# KC_BaseBoard4CompareTest.net
KiCad netlist of a schematic drawn in Altium Designer
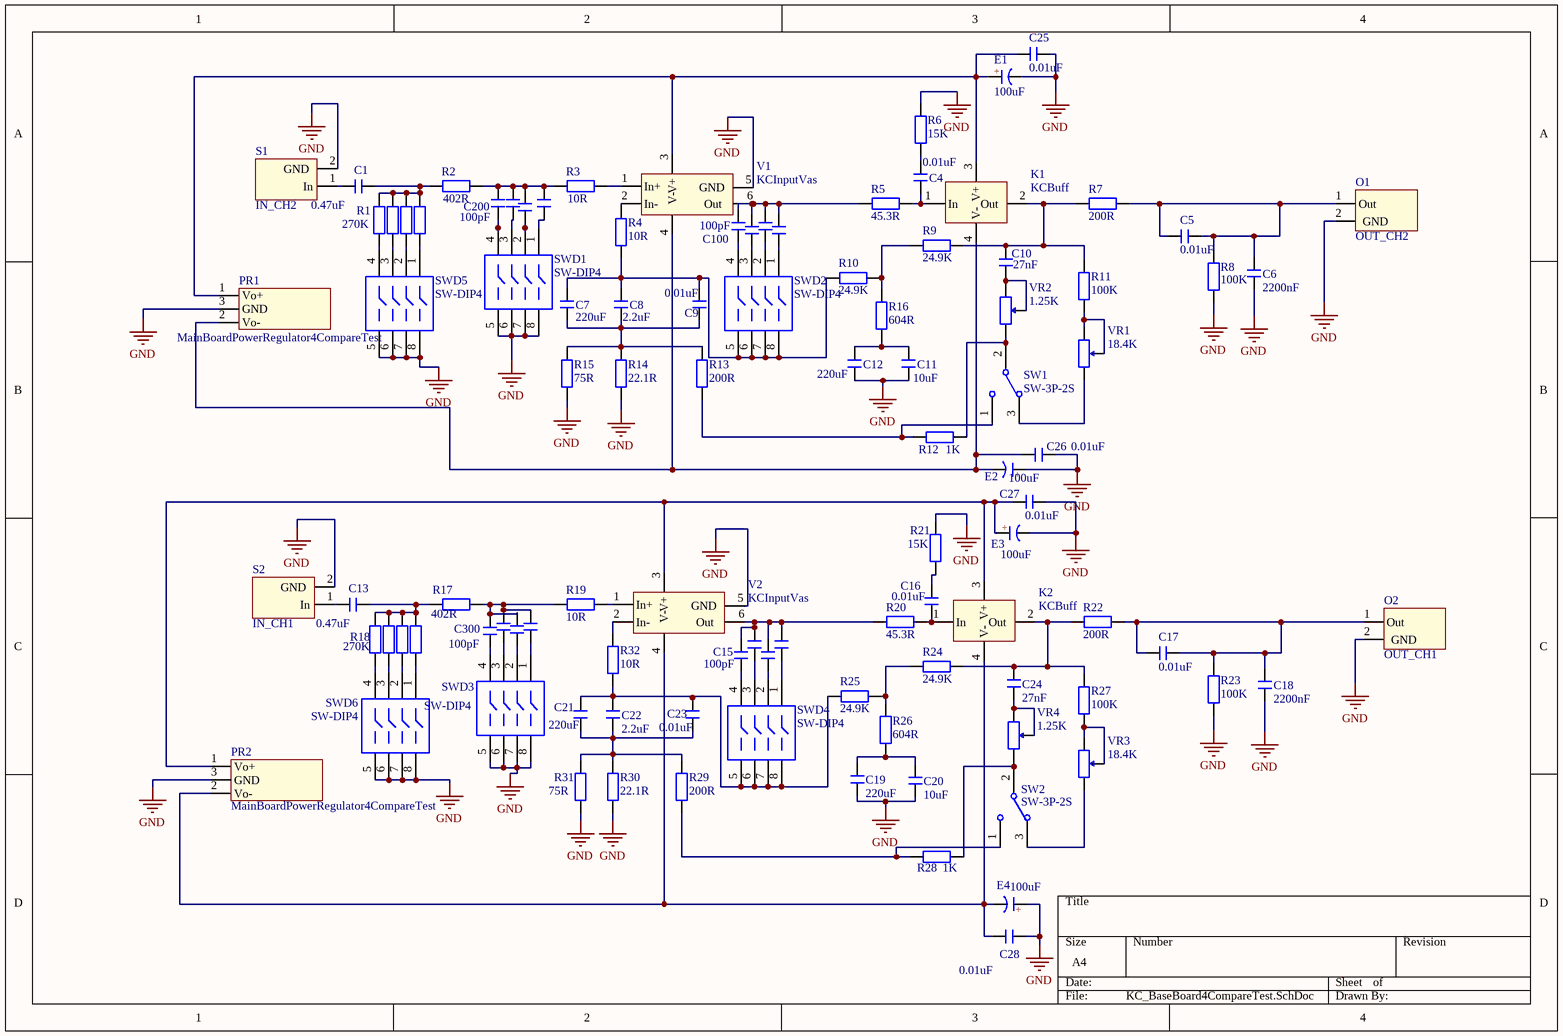
[diagram p0: KC_BaseBoard4CompareTest.SchDoc]

(export (version "E")
  (design (tool "Eeschema 10.0.6"))
  (components
    (comp (ref "C1")
      (value "0.47uF")
      (footprint "CBB 50*30*30")
      (description "CBB电容")
      (fields (field (name "版权归属") "源创客"))
      (libsource (lib "电阻-电容-电感") (part "C-CBB"))
    )
    (comp (ref "C4")
      (value "0.01uF")
      (footprint "CBB 6.3*6.3*5")
      (description "CBB电容")
      (fields (field (name "版权归属") "源创客"))
      (libsource (lib "电阻-电容-电感") (part "C-CBB"))
    )
    (comp (ref "C5")
      (value "0.01uF")
      (footprint "CBB 6.3*6.3*5")
      (description "CBB电容")
      (fields (field (name "版权归属") "源创客"))
      (libsource (lib "电阻-电容-电感") (part "C-CBB"))
    )
    (comp (ref "C6")
      (value "2200nF")
      (footprint "CBB 6.3*6.3*5")
      (description "CBB电容")
      (fields (field (name "版权归属") "源创客"))
      (libsource (lib "电阻-电容-电感") (part "C-CBB"))
    )
    (comp (ref "C7")
      (value "220uF")
      (footprint "CBB 6.3*6.3*5")
      (description "CBB电容")
      (fields (field (name "版权归属") "源创客"))
      (libsource (lib "电阻-电容-电感") (part "C-CBB"))
    )
    (comp (ref "C8")
      (value "2.2uF")
      (footprint "CBB 6.3*6.3*5")
      (description "CBB电容")
      (fields (field (name "版权归属") "源创客"))
      (libsource (lib "电阻-电容-电感") (part "C-CBB"))
    )
    (comp (ref "C9")
      (value "0.01uF")
      (footprint "CBB 6.3*6.3*5")
      (description "CBB电容")
      (fields (field (name "版权归属") "源创客"))
      (libsource (lib "电阻-电容-电感") (part "C-CBB"))
    )
    (comp (ref "C10")
      (value "27nF")
      (footprint "CBB 6.3*6.3*5")
      (description "CBB电容")
      (fields (field (name "版权归属") "源创客"))
      (libsource (lib "电阻-电容-电感") (part "C-CBB"))
    )
    (comp (ref "C11")
      (value "10uF")
      (footprint "CBB 6.3*6.3*5")
      (description "CBB电容")
      (fields (field (name "版权归属") "源创客"))
      (libsource (lib "电阻-电容-电感") (part "C-CBB"))
    )
    (comp (ref "C12")
      (value "220uF")
      (footprint "CBB 6.3*6.3*5")
      (description "CBB电容")
      (fields (field (name "版权归属") "源创客"))
      (libsource (lib "电阻-电容-电感") (part "C-CBB"))
    )
    (comp (ref "C13")
      (value "0.47uF")
      (footprint "CBB 50*30*30")
      (description "CBB电容")
      (fields (field (name "版权归属") "源创客"))
      (libsource (lib "电阻-电容-电感") (part "C-CBB"))
    )
    (comp (ref "C15")
      (value "100pF")
      (footprint "CBB 6.3*6.3*5")
      (description "CBB电容")
      (fields (field (name "版权归属") "源创客"))
      (libsource (lib "电阻-电容-电感") (part "C-CBB"))
    )
    (comp (ref "C16")
      (value "0.01uF")
      (footprint "CBB 6.3*6.3*5")
      (description "CBB电容")
      (fields (field (name "版权归属") "源创客"))
      (libsource (lib "电阻-电容-电感") (part "C-CBB"))
    )
    (comp (ref "C17")
      (value "0.01uF")
      (footprint "CBB 6.3*6.3*5")
      (description "CBB电容")
      (fields (field (name "版权归属") "源创客"))
      (libsource (lib "电阻-电容-电感") (part "C-CBB"))
    )
    (comp (ref "C18")
      (value "2200nF")
      (footprint "CBB 6.3*6.3*5")
      (description "CBB电容")
      (fields (field (name "版权归属") "源创客"))
      (libsource (lib "电阻-电容-电感") (part "C-CBB"))
    )
    (comp (ref "C19")
      (value "220uF")
      (footprint "CBB 6.3*6.3*5")
      (description "CBB电容")
      (fields (field (name "版权归属") "源创客"))
      (libsource (lib "电阻-电容-电感") (part "C-CBB"))
    )
    (comp (ref "C20")
      (value "10uF")
      (footprint "CBB 6.3*6.3*5")
      (description "CBB电容")
      (fields (field (name "版权归属") "源创客"))
      (libsource (lib "电阻-电容-电感") (part "C-CBB"))
    )
    (comp (ref "C21")
      (value "220uF")
      (footprint "CBB 6.3*6.3*5")
      (description "CBB电容")
      (fields (field (name "版权归属") "源创客"))
      (libsource (lib "电阻-电容-电感") (part "C-CBB"))
    )
    (comp (ref "C22")
      (value "2.2uF")
      (footprint "CBB 6.3*6.3*5")
      (description "CBB电容")
      (fields (field (name "版权归属") "源创客"))
      (libsource (lib "电阻-电容-电感") (part "C-CBB"))
    )
    (comp (ref "C23")
      (value "0.01uF")
      (footprint "CBB 6.3*6.3*5")
      (description "CBB电容")
      (fields (field (name "版权归属") "源创客"))
      (libsource (lib "电阻-电容-电感") (part "C-CBB"))
    )
    (comp (ref "C24")
      (value "27nF")
      (footprint "CBB 6.3*6.3*5")
      (description "CBB电容")
      (fields (field (name "版权归属") "源创客"))
      (libsource (lib "电阻-电容-电感") (part "C-CBB"))
    )
    (comp (ref "C25")
      (value "0.01uF")
      (footprint "CBB 6.3*6.3*5")
      (description "CBB电容")
      (fields (field (name "版权归属") "源创客"))
      (libsource (lib "电阻-电容-电感") (part "C-CBB"))
    )
    (comp (ref "C26")
      (value "0.01uF")
      (footprint "CBB 6.3*6.3*5")
      (description "CBB电容")
      (fields (field (name "版权归属") "源创客"))
      (libsource (lib "电阻-电容-电感") (part "C-CBB"))
    )
    (comp (ref "C27")
      (value "0.01uF")
      (footprint "CBB 6.3*6.3*5")
      (description "CBB电容")
      (fields (field (name "版权归属") "源创客"))
      (libsource (lib "电阻-电容-电感") (part "C-CBB"))
    )
    (comp (ref "C28")
      (value "0.01uF")
      (footprint "CBB 6.3*6.3*5")
      (description "CBB电容")
      (fields (field (name "版权归属") "源创客"))
      (libsource (lib "电阻-电容-电感") (part "C-CBB"))
    )
    (comp (ref "C100")
      (value "100pF")
      (footprint "CBB 6.3*6.3*5")
      (description "CBB电容")
      (fields (field (name "版权归属") "源创客"))
      (libsource (lib "电阻-电容-电感") (part "C-CBB"))
    )
    (comp (ref "C101")
      (value "100pF")
      (footprint "CBB 6.3*6.3*5")
      (description "CBB电容")
      (fields (field (name "版权归属") "源创客"))
      (libsource (lib "电阻-电容-电感") (part "C-CBB"))
    )
    (comp (ref "C102")
      (value "100pF")
      (footprint "CBB 6.3*6.3*5")
      (description "CBB电容")
      (fields (field (name "版权归属") "源创客"))
      (libsource (lib "电阻-电容-电感") (part "C-CBB"))
    )
    (comp (ref "C103")
      (value "20pF")
      (footprint "CBB 6.3*6.3*5")
      (description "CBB电容")
      (fields (field (name "版权归属") "源创客"))
      (libsource (lib "电阻-电容-电感") (part "C-CBB"))
    )
    (comp (ref "C200")
      (value "100pF")
      (footprint "CBB 6.3*6.3*5")
      (description "CBB电容")
      (fields (field (name "版权归属") "源创客"))
      (libsource (lib "电阻-电容-电感") (part "C-CBB"))
    )
    (comp (ref "C201")
      (value "100pF")
      (footprint "CBB 6.3*6.3*5")
      (description "CBB电容")
      (fields (field (name "版权归属") "源创客"))
      (libsource (lib "电阻-电容-电感") (part "C-CBB"))
    )
    (comp (ref "C202")
      (value "100pF")
      (footprint "CBB 6.3*6.3*5")
      (description "CBB电容")
      (fields (field (name "版权归属") "源创客"))
      (libsource (lib "电阻-电容-电感") (part "C-CBB"))
    )
    (comp (ref "C203")
      (value "20pF")
      (footprint "CBB 6.3*6.3*5")
      (description "CBB电容")
      (fields (field (name "版权归属") "源创客"))
      (libsource (lib "电阻-电容-电感") (part "C-CBB"))
    )
    (comp (ref "C300")
      (value "100pF")
      (footprint "CBB 6.3*6.3*5")
      (description "CBB电容")
      (fields (field (name "版权归属") "源创客"))
      (libsource (lib "电阻-电容-电感") (part "C-CBB"))
    )
    (comp (ref "C301")
      (value "100pF")
      (footprint "CBB 6.3*6.3*5")
      (description "CBB电容")
      (fields (field (name "版权归属") "源创客"))
      (libsource (lib "电阻-电容-电感") (part "C-CBB"))
    )
    (comp (ref "C302")
      (value "100pF")
      (footprint "CBB 6.3*6.3*5")
      (description "CBB电容")
      (fields (field (name "版权归属") "源创客"))
      (libsource (lib "电阻-电容-电感") (part "C-CBB"))
    )
    (comp (ref "C303")
      (value "20pF")
      (footprint "CBB 6.3*6.3*5")
      (description "CBB电容")
      (fields (field (name "版权归属") "源创客"))
      (libsource (lib "电阻-电容-电感") (part "C-CBB"))
    )
    (comp (ref "C401")
      (value "100pF")
      (footprint "CBB 6.3*6.3*5")
      (description "CBB电容")
      (fields (field (name "版权归属") "源创客"))
      (libsource (lib "电阻-电容-电感") (part "C-CBB"))
    )
    (comp (ref "C402")
      (value "100pF")
      (footprint "CBB 6.3*6.3*5")
      (description "CBB电容")
      (fields (field (name "版权归属") "源创客"))
      (libsource (lib "电阻-电容-电感") (part "C-CBB"))
    )
    (comp (ref "C403")
      (value "20pF")
      (footprint "CBB 6.3*6.3*5")
      (description "CBB电容")
      (fields (field (name "版权归属") "源创客"))
      (libsource (lib "电阻-电容-电感") (part "C-CBB"))
    )
    (comp (ref "E1")
      (value "100uF")
      (footprint "CAP 5.0*10*20")
      (description "直插电解电容")
      (fields (field (name "版权归属") "源创客"))
      (libsource (lib "电阻-电容-电感") (part "C-CAP"))
    )
    (comp (ref "E2")
      (value "100uF")
      (footprint "CAP 5.0*10*20")
      (description "直插电解电容")
      (fields (field (name "版权归属") "源创客"))
      (libsource (lib "电阻-电容-电感") (part "C-CAP"))
    )
    (comp (ref "E3")
      (value "100uF")
      (footprint "CAP 5.0*10*20")
      (description "直插电解电容")
      (fields (field (name "版权归属") "源创客"))
      (libsource (lib "电阻-电容-电感") (part "C-CAP"))
    )
    (comp (ref "E4")
      (value "100uF")
      (footprint "CAP 5.0*10*20")
      (description "直插电解电容")
      (fields (field (name "版权归属") "源创客"))
      (libsource (lib "电阻-电容-电感") (part "C-CAP"))
    )
    (comp (ref "K1")
      (value "KCBuff")
      (footprint "KCBuff_M4")
      (description "King Cello Buffer Stage")
      (libsource (lib "KC_amp") (part "KCBuff"))
    )
    (comp (ref "K2")
      (value "KCBuff")
      (footprint "KCBuff_M4")
      (description "King Cello Buffer Stage")
      (libsource (lib "KC_amp") (part "KCBuff"))
    )
    (comp (ref "O1")
      (value "OUT_CH2")
      (footprint "Signal_Terminal")
      (description "Signal Out")
      (libsource (lib "KC_amp") (part "Signal_Out"))
    )
    (comp (ref "O2")
      (value "OUT_CH1")
      (footprint "Signal_Terminal")
      (description "Signal Out")
      (libsource (lib "KC_amp") (part "Signal_Out"))
    )
    (comp (ref "PR1")
      (value "MainBoardPowerRegulator4CompareTest")
      (footprint "KC_MBPowerReg4Compare")
      (description "King Cello Compare Test Power")
      (libsource (lib "KC_amp") (part "MainBoardPowerRegulator4CompareTest"))
    )
    (comp (ref "PR2")
      (value "MainBoardPowerRegulator4CompareTest")
      (footprint "KC_MBPowerReg4Compare")
      (description "King Cello Compare Test Power")
      (libsource (lib "KC_amp") (part "MainBoardPowerRegulator4CompareTest"))
    )
    (comp (ref "R1")
      (value "270K")
      (footprint "RS 1/2W")
      (description "直插色环电阻")
      (fields (field (name "版权归属") "源创客"))
      (libsource (lib "电阻-电容-电感") (part "R-CRR"))
    )
    (comp (ref "R2")
      (value "402R")
      (footprint "RS 1/2W")
      (description "直插色环电阻")
      (fields (field (name "版权归属") "源创客"))
      (libsource (lib "电阻-电容-电感") (part "R-CRR"))
    )
    (comp (ref "R3")
      (value "10R")
      (footprint "RS 1/2W")
      (description "直插色环电阻")
      (fields (field (name "版权归属") "源创客"))
      (libsource (lib "电阻-电容-电感") (part "R-CRR"))
    )
    (comp (ref "R4")
      (value "10R")
      (footprint "RS 1/2W")
      (description "直插色环电阻")
      (fields (field (name "版权归属") "源创客"))
      (libsource (lib "电阻-电容-电感") (part "R-CRR"))
    )
    (comp (ref "R5")
      (value "45.3R")
      (footprint "RS 1/2W")
      (description "直插色环电阻")
      (fields (field (name "版权归属") "源创客"))
      (libsource (lib "电阻-电容-电感") (part "R-CRR"))
    )
    (comp (ref "R6")
      (value "15K")
      (footprint "RS 1/2W")
      (description "直插色环电阻")
      (fields (field (name "版权归属") "源创客"))
      (libsource (lib "电阻-电容-电感") (part "R-CRR"))
    )
    (comp (ref "R7")
      (value "200R")
      (footprint "RS 1W")
      (description "直插色环电阻")
      (fields (field (name "版权归属") "源创客"))
      (libsource (lib "电阻-电容-电感") (part "R-CRR"))
    )
    (comp (ref "R8")
      (value "100K")
      (footprint "RS 1/2W")
      (description "直插色环电阻")
      (fields (field (name "版权归属") "源创客"))
      (libsource (lib "电阻-电容-电感") (part "R-CRR"))
    )
    (comp (ref "R9")
      (value "24.9K")
      (footprint "RS 1/2W")
      (description "直插色环电阻")
      (fields (field (name "版权归属") "源创客"))
      (libsource (lib "电阻-电容-电感") (part "R-CRR"))
    )
    (comp (ref "R10")
      (value "24.9K")
      (footprint "RS 1/2W")
      (description "直插色环电阻")
      (fields (field (name "版权归属") "源创客"))
      (libsource (lib "电阻-电容-电感") (part "R-CRR"))
    )
    (comp (ref "R11")
      (value "100K")
      (footprint "RS 1/2W")
      (description "直插色环电阻")
      (fields (field (name "版权归属") "源创客"))
      (libsource (lib "电阻-电容-电感") (part "R-CRR"))
    )
    (comp (ref "R12")
      (value "1K")
      (footprint "RS 1/2W")
      (description "直插色环电阻")
      (fields (field (name "版权归属") "源创客"))
      (libsource (lib "电阻-电容-电感") (part "R-CRR"))
    )
    (comp (ref "R13")
      (value "200R")
      (footprint "RS 1/2W")
      (description "直插色环电阻")
      (fields (field (name "版权归属") "源创客"))
      (libsource (lib "电阻-电容-电感") (part "R-CRR"))
    )
    (comp (ref "R14")
      (value "22.1R")
      (footprint "RS 1/2W")
      (description "直插色环电阻")
      (fields (field (name "版权归属") "源创客"))
      (libsource (lib "电阻-电容-电感") (part "R-CRR"))
    )
    (comp (ref "R15")
      (value "75R")
      (footprint "RS 1/2W")
      (description "直插色环电阻")
      (fields (field (name "版权归属") "源创客"))
      (libsource (lib "电阻-电容-电感") (part "R-CRR"))
    )
    (comp (ref "R16")
      (value "604R")
      (footprint "RS 1W")
      (description "直插色环电阻")
      (fields (field (name "版权归属") "源创客"))
      (libsource (lib "电阻-电容-电感") (part "R-CRR"))
    )
    (comp (ref "R17")
      (value "402R")
      (footprint "RS 1/2W")
      (description "直插色环电阻")
      (fields (field (name "版权归属") "源创客"))
      (libsource (lib "电阻-电容-电感") (part "R-CRR"))
    )
    (comp (ref "R18")
      (value "270K")
      (footprint "RS 1/2W")
      (description "直插色环电阻")
      (fields (field (name "版权归属") "源创客"))
      (libsource (lib "电阻-电容-电感") (part "R-CRR"))
    )
    (comp (ref "R19")
      (value "10R")
      (footprint "RS 1/2W")
      (description "直插色环电阻")
      (fields (field (name "版权归属") "源创客"))
      (libsource (lib "电阻-电容-电感") (part "R-CRR"))
    )
    (comp (ref "R20")
      (value "45.3R")
      (footprint "RS 1/2W")
      (description "直插色环电阻")
      (fields (field (name "版权归属") "源创客"))
      (libsource (lib "电阻-电容-电感") (part "R-CRR"))
    )
    (comp (ref "R21")
      (value "15K")
      (footprint "RS 1/2W")
      (description "直插色环电阻")
      (fields (field (name "版权归属") "源创客"))
      (libsource (lib "电阻-电容-电感") (part "R-CRR"))
    )
    (comp (ref "R22")
      (value "200R")
      (footprint "RS 1W")
      (description "直插色环电阻")
      (fields (field (name "版权归属") "源创客"))
      (libsource (lib "电阻-电容-电感") (part "R-CRR"))
    )
    (comp (ref "R23")
      (value "100K")
      (footprint "RS 1/2W")
      (description "直插色环电阻")
      (fields (field (name "版权归属") "源创客"))
      (libsource (lib "电阻-电容-电感") (part "R-CRR"))
    )
    (comp (ref "R24")
      (value "24.9K")
      (footprint "RS 1/2W")
      (description "直插色环电阻")
      (fields (field (name "版权归属") "源创客"))
      (libsource (lib "电阻-电容-电感") (part "R-CRR"))
    )
    (comp (ref "R25")
      (value "24.9K")
      (footprint "RS 1/2W")
      (description "直插色环电阻")
      (fields (field (name "版权归属") "源创客"))
      (libsource (lib "电阻-电容-电感") (part "R-CRR"))
    )
    (comp (ref "R26")
      (value "604R")
      (footprint "RS 1W")
      (description "直插色环电阻")
      (fields (field (name "版权归属") "源创客"))
      (libsource (lib "电阻-电容-电感") (part "R-CRR"))
    )
    (comp (ref "R27")
      (value "100K")
      (footprint "RS 1/2W")
      (description "直插色环电阻")
      (fields (field (name "版权归属") "源创客"))
      (libsource (lib "电阻-电容-电感") (part "R-CRR"))
    )
    (comp (ref "R28")
      (value "1K")
      (footprint "RS 1/2W")
      (description "直插色环电阻")
      (fields (field (name "版权归属") "源创客"))
      (libsource (lib "电阻-电容-电感") (part "R-CRR"))
    )
    (comp (ref "R29")
      (value "200R")
      (footprint "RS 1/2W")
      (description "直插色环电阻")
      (fields (field (name "版权归属") "源创客"))
      (libsource (lib "电阻-电容-电感") (part "R-CRR"))
    )
    (comp (ref "R30")
      (value "22.1R")
      (footprint "RS 1/2W")
      (description "直插色环电阻")
      (fields (field (name "版权归属") "源创客"))
      (libsource (lib "电阻-电容-电感") (part "R-CRR"))
    )
    (comp (ref "R31")
      (value "75R")
      (footprint "RS 1/2W")
      (description "直插色环电阻")
      (fields (field (name "版权归属") "源创客"))
      (libsource (lib "电阻-电容-电感") (part "R-CRR"))
    )
    (comp (ref "R32")
      (value "10R")
      (footprint "RS 1/2W")
      (description "直插色环电阻")
      (fields (field (name "版权归属") "源创客"))
      (libsource (lib "电阻-电容-电感") (part "R-CRR"))
    )
    (comp (ref "R101")
      (value "182K")
      (footprint "RS 1/2W")
      (description "直插色环电阻")
      (fields (field (name "版权归属") "源创客"))
      (libsource (lib "电阻-电容-电感") (part "R-CRR"))
    )
    (comp (ref "R102")
      (value "100K")
      (footprint "RS 1/2W")
      (description "直插色环电阻")
      (fields (field (name "版权归属") "源创客"))
      (libsource (lib "电阻-电容-电感") (part "R-CRR"))
    )
    (comp (ref "R103")
      (value "47K")
      (footprint "RS 1/2W")
      (description "直插色环电阻")
      (fields (field (name "版权归属") "源创客"))
      (libsource (lib "电阻-电容-电感") (part "R-CRR"))
    )
    (comp (ref "R181")
      (value "182K")
      (footprint "RS 1/2W")
      (description "直插色环电阻")
      (fields (field (name "版权归属") "源创客"))
      (libsource (lib "电阻-电容-电感") (part "R-CRR"))
    )
    (comp (ref "R182")
      (value "100K")
      (footprint "RS 1/2W")
      (description "直插色环电阻")
      (fields (field (name "版权归属") "源创客"))
      (libsource (lib "电阻-电容-电感") (part "R-CRR"))
    )
    (comp (ref "R183")
      (value "47K")
      (footprint "RS 1/2W")
      (description "直插色环电阻")
      (fields (field (name "版权归属") "源创客"))
      (libsource (lib "电阻-电容-电感") (part "R-CRR"))
    )
    (comp (ref "S1")
      (value "IN_CH2")
      (footprint "Signal_Terminal")
      (description "Signal In")
      (libsource (lib "KC_amp") (part "Signal_In"))
    )
    (comp (ref "S2")
      (value "IN_CH1")
      (footprint "Signal_Terminal")
      (description "Signal In")
      (libsource (lib "KC_amp") (part "Signal_In"))
    )
    (comp (ref "SW1")
      (value "SW-3P-2S")
      (footprint "SS-12D06")
      (description "3 Pin 2 Switch")
      (libsource (lib "Connectors") (part "SW-3P-2S"))
    )
    (comp (ref "SW2")
      (value "SW-3P-2S")
      (footprint "SS-12D06")
      (description "3 Pin 2 Switch")
      (libsource (lib "Connectors") (part "SW-3P-2S"))
    )
    (comp (ref "SWD1")
      (value "SW-DIP4")
      (footprint "DIP-8")
      (description "DIP Switch")
      (fields (field (name "PUBLISHER") "Altium Limited"))
      (libsource (lib "Miscellaneous Devices") (part "SW-DIP4"))
    )
    (comp (ref "SWD2")
      (value "SW-DIP4")
      (footprint "DIP-8")
      (description "DIP Switch")
      (fields (field (name "PUBLISHER") "Altium Limited"))
      (libsource (lib "Miscellaneous Devices") (part "SW-DIP4"))
    )
    (comp (ref "SWD3")
      (value "SW-DIP4")
      (footprint "DIP-8")
      (description "DIP Switch")
      (fields (field (name "PUBLISHER") "Altium Limited"))
      (libsource (lib "Miscellaneous Devices") (part "SW-DIP4"))
    )
    (comp (ref "SWD4")
      (value "SW-DIP4")
      (footprint "DIP-8")
      (description "DIP Switch")
      (fields (field (name "PUBLISHER") "Altium Limited"))
      (libsource (lib "Miscellaneous Devices") (part "SW-DIP4"))
    )
    (comp (ref "SWD5")
      (value "SW-DIP4")
      (footprint "DIP-8")
      (description "DIP Switch")
      (fields (field (name "PUBLISHER") "Altium Limited"))
      (libsource (lib "Miscellaneous Devices") (part "SW-DIP4"))
    )
    (comp (ref "SWD6")
      (value "SW-DIP4")
      (footprint "DIP-8")
      (description "DIP Switch")
      (fields (field (name "PUBLISHER") "Altium Limited"))
      (libsource (lib "Miscellaneous Devices") (part "SW-DIP4"))
    )
    (comp (ref "V1")
      (value "KCInputVas")
      (footprint "KCIn_VAS_M4")
      (description "King Cello Input Stage and VAS")
      (libsource (lib "KC_amp") (part "KCInputVas"))
    )
    (comp (ref "V2")
      (value "KCInputVas")
      (footprint "KCIn_VAS_M4")
      (description "King Cello Input Stage and VAS")
      (libsource (lib "KC_amp") (part "KCInputVas"))
    )
    (comp (ref "VR1")
      (value "18.4K")
      (footprint "RS 1/2W-VR")
      (description "直插可调电阻-顶调")
      (libsource (lib "电阻-电容-电感") (part "VR-W"))
    )
    (comp (ref "VR2")
      (value "1.25K")
      (footprint "RS 1/2W-VR")
      (description "直插可调电阻-顶调")
      (libsource (lib "电阻-电容-电感") (part "VR-W"))
    )
    (comp (ref "VR3")
      (value "18.4K")
      (footprint "RS 1/2W-VR")
      (description "直插可调电阻-顶调")
      (libsource (lib "电阻-电容-电感") (part "VR-W"))
    )
    (comp (ref "VR4")
      (value "1.25K")
      (footprint "RS 1/2W-VR")
      (description "直插可调电阻-顶调")
      (libsource (lib "电阻-电容-电感") (part "VR-W"))
    )
  )
  (nets
    (net (code "1") (name "GND") (class "Default")
      (node (ref "C11") (pin "1") (pinfunction "1_1") (pintype "passive"))
      (node (ref "C12") (pin "1") (pinfunction "1_1") (pintype "passive"))
      (node (ref "C18") (pin "2") (pinfunction "2_2") (pintype "passive"))
      (node (ref "C19") (pin "2") (pinfunction "2_2") (pintype "passive"))
      (node (ref "C20") (pin "2") (pinfunction "2_2") (pintype "passive"))
      (node (ref "C25") (pin "2") (pinfunction "2_2") (pintype "passive"))
      (node (ref "C26") (pin "2") (pinfunction "2_2") (pintype "passive"))
      (node (ref "C27") (pin "2") (pinfunction "2_2") (pintype "passive"))
      (node (ref "C28") (pin "2") (pinfunction "2_2") (pintype "passive"))
      (node (ref "C6") (pin "1") (pinfunction "1_1") (pintype "passive"))
      (node (ref "E1") (pin "2") (pinfunction "K_2") (pintype "passive"))
      (node (ref "E2") (pin "1") (pinfunction "A_1") (pintype "passive"))
      (node (ref "E3") (pin "2") (pinfunction "K_2") (pintype "passive"))
      (node (ref "E4") (pin "1") (pinfunction "A_1") (pintype "passive"))
      (node (ref "O1") (pin "2") (pinfunction "GND_2") (pintype "passive"))
      (node (ref "O2") (pin "2") (pinfunction "GND_2") (pintype "passive"))
      (node (ref "PR1") (pin "3") (pinfunction "GND_3") (pintype "passive"))
      (node (ref "PR2") (pin "3") (pinfunction "GND_3") (pintype "passive"))
      (node (ref "R14") (pin "1") (pinfunction "1_1") (pintype "passive"))
      (node (ref "R15") (pin "1") (pinfunction "1_1") (pintype "passive"))
      (node (ref "R21") (pin "2") (pinfunction "2_2") (pintype "passive"))
      (node (ref "R23") (pin "2") (pinfunction "2_2") (pintype "passive"))
      (node (ref "R30") (pin "1") (pinfunction "1_1") (pintype "passive"))
      (node (ref "R31") (pin "1") (pinfunction "1_1") (pintype "passive"))
      (node (ref "R6") (pin "1") (pinfunction "1_1") (pintype "passive"))
      (node (ref "R8") (pin "1") (pinfunction "1_1") (pintype "passive"))
      (node (ref "S1") (pin "2") (pinfunction "GND_2") (pintype "passive"))
      (node (ref "S2") (pin "2") (pinfunction "GND_2") (pintype "passive"))
      (node (ref "SWD1") (pin "5") (pinfunction "5_5") (pintype "passive"))
      (node (ref "SWD1") (pin "6") (pinfunction "6_6") (pintype "passive"))
      (node (ref "SWD1") (pin "7") (pinfunction "7_7") (pintype "passive"))
      (node (ref "SWD1") (pin "8") (pinfunction "8_8") (pintype "passive"))
      (node (ref "SWD3") (pin "5") (pinfunction "5_5") (pintype "passive"))
      (node (ref "SWD3") (pin "6") (pinfunction "6_6") (pintype "passive"))
      (node (ref "SWD3") (pin "7") (pinfunction "7_7") (pintype "passive"))
      (node (ref "SWD3") (pin "8") (pinfunction "8_8") (pintype "passive"))
      (node (ref "SWD5") (pin "5") (pinfunction "5_5") (pintype "passive"))
      (node (ref "SWD5") (pin "6") (pinfunction "6_6") (pintype "passive"))
      (node (ref "SWD5") (pin "7") (pinfunction "7_7") (pintype "passive"))
      (node (ref "SWD5") (pin "8") (pinfunction "8_8") (pintype "passive"))
      (node (ref "SWD6") (pin "5") (pinfunction "5_5") (pintype "passive"))
      (node (ref "SWD6") (pin "6") (pinfunction "6_6") (pintype "passive"))
      (node (ref "SWD6") (pin "7") (pinfunction "7_7") (pintype "passive"))
      (node (ref "SWD6") (pin "8") (pinfunction "8_8") (pintype "passive"))
      (node (ref "V1") (pin "5") (pinfunction "GND_5") (pintype "passive"))
      (node (ref "V2") (pin "5") (pinfunction "GND_5") (pintype "passive"))
    )
    (net (code "2") (name "Net-(C1-Pad2)") (class "Default")
      (node (ref "C1") (pin "2") (pinfunction "2_2") (pintype "passive"))
      (node (ref "R1") (pin "2") (pinfunction "2_2") (pintype "passive"))
      (node (ref "R101") (pin "2") (pinfunction "2_2") (pintype "passive"))
      (node (ref "R102") (pin "2") (pinfunction "2_2") (pintype "passive"))
      (node (ref "R103") (pin "2") (pinfunction "2_2") (pintype "passive"))
      (node (ref "R2") (pin "1") (pinfunction "1_1") (pintype "passive"))
    )
    (net (code "3") (name "Net-(C4-Pad2)") (class "Default")
      (node (ref "C4") (pin "2") (pinfunction "2_2") (pintype "passive"))
      (node (ref "R6") (pin "2") (pinfunction "2_2") (pintype "passive"))
    )
    (net (code "4") (name "Net-(C7-Pad1)") (class "Default")
      (node (ref "C7") (pin "1") (pinfunction "1_1") (pintype "passive"))
      (node (ref "C8") (pin "1") (pinfunction "1_1") (pintype "passive"))
      (node (ref "C9") (pin "1") (pinfunction "1_1") (pintype "passive"))
      (node (ref "R13") (pin "2") (pinfunction "2_2") (pintype "passive"))
      (node (ref "R14") (pin "2") (pinfunction "2_2") (pintype "passive"))
      (node (ref "R15") (pin "2") (pinfunction "2_2") (pintype "passive"))
    )
    (net (code "5") (name "Net-(C7-Pad2)") (class "Default")
      (node (ref "C7") (pin "2") (pinfunction "2_2") (pintype "passive"))
      (node (ref "C8") (pin "2") (pinfunction "2_2") (pintype "passive"))
      (node (ref "C9") (pin "2") (pinfunction "2_2") (pintype "passive"))
      (node (ref "R10") (pin "2") (pinfunction "2_2") (pintype "passive"))
      (node (ref "R4") (pin "1") (pinfunction "1_1") (pintype "passive"))
      (node (ref "SWD2") (pin "5") (pinfunction "5_5") (pintype "passive"))
      (node (ref "SWD2") (pin "6") (pinfunction "6_6") (pintype "passive"))
      (node (ref "SWD2") (pin "7") (pinfunction "7_7") (pintype "passive"))
      (node (ref "SWD2") (pin "8") (pinfunction "8_8") (pintype "passive"))
    )
    (net (code "6") (name "Net-(C10-Pad1)") (class "Default")
      (node (ref "C10") (pin "1") (pinfunction "1_1") (pintype "passive"))
      (node (ref "VR2") (pin "1") (pinfunction "1_1") (pintype "passive"))
      (node (ref "VR2") (pin "3") (pinfunction "3_3") (pintype "passive"))
    )
    (net (code "7") (name "Net-(C11-Pad2)") (class "Default")
      (node (ref "C11") (pin "2") (pinfunction "2_2") (pintype "passive"))
      (node (ref "C12") (pin "2") (pinfunction "2_2") (pintype "passive"))
      (node (ref "R16") (pin "1") (pinfunction "1_1") (pintype "passive"))
    )
    (net (code "8") (name "Net-(C13-Pad2)") (class "Default")
      (node (ref "C13") (pin "2") (pinfunction "2_2") (pintype "passive"))
      (node (ref "R17") (pin "1") (pinfunction "1_1") (pintype "passive"))
      (node (ref "R18") (pin "2") (pinfunction "2_2") (pintype "passive"))
      (node (ref "R181") (pin "2") (pinfunction "2_2") (pintype "passive"))
      (node (ref "R182") (pin "2") (pinfunction "2_2") (pintype "passive"))
      (node (ref "R183") (pin "2") (pinfunction "2_2") (pintype "passive"))
    )
    (net (code "9") (name "Net-(C15-Pad1)") (class "Default")
      (node (ref "C15") (pin "1") (pinfunction "1_1") (pintype "passive"))
      (node (ref "SWD4") (pin "4") (pinfunction "4_4") (pintype "passive"))
    )
    (net (code "10") (name "Net-(C16-Pad2)") (class "Default")
      (node (ref "C16") (pin "2") (pinfunction "2_2") (pintype "passive"))
      (node (ref "R21") (pin "1") (pinfunction "1_1") (pintype "passive"))
    )
    (net (code "11") (name "Net-(C19-Pad1)") (class "Default")
      (node (ref "C19") (pin "1") (pinfunction "1_1") (pintype "passive"))
      (node (ref "C20") (pin "1") (pinfunction "1_1") (pintype "passive"))
      (node (ref "R26") (pin "1") (pinfunction "1_1") (pintype "passive"))
    )
    (net (code "12") (name "Net-(C21-Pad1)") (class "Default")
      (node (ref "C21") (pin "1") (pinfunction "1_1") (pintype "passive"))
      (node (ref "C22") (pin "1") (pinfunction "1_1") (pintype "passive"))
      (node (ref "C23") (pin "1") (pinfunction "1_1") (pintype "passive"))
      (node (ref "R25") (pin "1") (pinfunction "1_1") (pintype "passive"))
      (node (ref "R32") (pin "1") (pinfunction "1_1") (pintype "passive"))
      (node (ref "SWD4") (pin "5") (pinfunction "5_5") (pintype "passive"))
      (node (ref "SWD4") (pin "6") (pinfunction "6_6") (pintype "passive"))
      (node (ref "SWD4") (pin "7") (pinfunction "7_7") (pintype "passive"))
      (node (ref "SWD4") (pin "8") (pinfunction "8_8") (pintype "passive"))
    )
    (net (code "13") (name "Net-(C21-Pad2)") (class "Default")
      (node (ref "C21") (pin "2") (pinfunction "2_2") (pintype "passive"))
      (node (ref "C22") (pin "2") (pinfunction "2_2") (pintype "passive"))
      (node (ref "C23") (pin "2") (pinfunction "2_2") (pintype "passive"))
      (node (ref "R29") (pin "2") (pinfunction "2_2") (pintype "passive"))
      (node (ref "R30") (pin "2") (pinfunction "2_2") (pintype "passive"))
      (node (ref "R31") (pin "2") (pinfunction "2_2") (pintype "passive"))
    )
    (net (code "14") (name "Net-(C24-Pad2)") (class "Default")
      (node (ref "C24") (pin "2") (pinfunction "2_2") (pintype "passive"))
      (node (ref "VR4") (pin "1") (pinfunction "1_1") (pintype "passive"))
      (node (ref "VR4") (pin "3") (pinfunction "3_3") (pintype "passive"))
    )
    (net (code "15") (name "Net-(C100-Pad1)") (class "Default")
      (node (ref "C100") (pin "1") (pinfunction "1_1") (pintype "passive"))
      (node (ref "SWD2") (pin "4") (pinfunction "4_4") (pintype "passive"))
    )
    (net (code "16") (name "Net-(C101-Pad1)") (class "Default")
      (node (ref "C101") (pin "1") (pinfunction "1_1") (pintype "passive"))
      (node (ref "SWD2") (pin "3") (pinfunction "3_3") (pintype "passive"))
    )
    (net (code "17") (name "Net-(C102-Pad1)") (class "Default")
      (node (ref "C102") (pin "1") (pinfunction "1_1") (pintype "passive"))
      (node (ref "SWD2") (pin "2") (pinfunction "2_2") (pintype "passive"))
    )
    (net (code "18") (name "Net-(C103-Pad1)") (class "Default")
      (node (ref "C103") (pin "1") (pinfunction "1_1") (pintype "passive"))
      (node (ref "SWD2") (pin "1") (pinfunction "1_1") (pintype "passive"))
    )
    (net (code "19") (name "Net-(C200-Pad1)") (class "Default")
      (node (ref "C200") (pin "1") (pinfunction "1_1") (pintype "passive"))
      (node (ref "SWD1") (pin "4") (pinfunction "4_4") (pintype "passive"))
    )
    (net (code "20") (name "Net-(C200-Pad2)") (class "Default")
      (node (ref "C200") (pin "2") (pinfunction "2_2") (pintype "passive"))
      (node (ref "C201") (pin "2") (pinfunction "2_2") (pintype "passive"))
      (node (ref "C202") (pin "2") (pinfunction "2_2") (pintype "passive"))
      (node (ref "C203") (pin "2") (pinfunction "2_2") (pintype "passive"))
      (node (ref "R2") (pin "2") (pinfunction "2_2") (pintype "passive"))
      (node (ref "R3") (pin "2") (pinfunction "2_2") (pintype "passive"))
    )
    (net (code "21") (name "Net-(C201-Pad1)") (class "Default")
      (node (ref "C201") (pin "1") (pinfunction "1_1") (pintype "passive"))
      (node (ref "SWD1") (pin "3") (pinfunction "3_3") (pintype "passive"))
    )
    (net (code "22") (name "Net-(C202-Pad1)") (class "Default")
      (node (ref "C202") (pin "1") (pinfunction "1_1") (pintype "passive"))
      (node (ref "SWD1") (pin "2") (pinfunction "2_2") (pintype "passive"))
    )
    (net (code "23") (name "Net-(C203-Pad1)") (class "Default")
      (node (ref "C203") (pin "1") (pinfunction "1_1") (pintype "passive"))
      (node (ref "SWD1") (pin "1") (pinfunction "1_1") (pintype "passive"))
    )
    (net (code "24") (name "Net-(C300-Pad1)") (class "Default")
      (node (ref "C300") (pin "1") (pinfunction "1_1") (pintype "passive"))
      (node (ref "SWD3") (pin "4") (pinfunction "4_4") (pintype "passive"))
    )
    (net (code "25") (name "Net-(C300-Pad2)") (class "Default")
      (node (ref "C300") (pin "2") (pinfunction "2_2") (pintype "passive"))
      (node (ref "C301") (pin "2") (pinfunction "2_2") (pintype "passive"))
      (node (ref "C302") (pin "2") (pinfunction "2_2") (pintype "passive"))
      (node (ref "C303") (pin "2") (pinfunction "2_2") (pintype "passive"))
      (node (ref "R17") (pin "2") (pinfunction "2_2") (pintype "passive"))
      (node (ref "R19") (pin "1") (pinfunction "1_1") (pintype "passive"))
    )
    (net (code "26") (name "Net-(C301-Pad1)") (class "Default")
      (node (ref "C301") (pin "1") (pinfunction "1_1") (pintype "passive"))
      (node (ref "SWD3") (pin "3") (pinfunction "3_3") (pintype "passive"))
    )
    (net (code "27") (name "Net-(C302-Pad1)") (class "Default")
      (node (ref "C302") (pin "1") (pinfunction "1_1") (pintype "passive"))
      (node (ref "SWD3") (pin "2") (pinfunction "2_2") (pintype "passive"))
    )
    (net (code "28") (name "Net-(C303-Pad1)") (class "Default")
      (node (ref "C303") (pin "1") (pinfunction "1_1") (pintype "passive"))
      (node (ref "SWD3") (pin "1") (pinfunction "1_1") (pintype "passive"))
    )
    (net (code "29") (name "Net-(C401-Pad1)") (class "Default")
      (node (ref "C401") (pin "1") (pinfunction "1_1") (pintype "passive"))
      (node (ref "SWD4") (pin "3") (pinfunction "3_3") (pintype "passive"))
    )
    (net (code "30") (name "Net-(C402-Pad1)") (class "Default")
      (node (ref "C402") (pin "1") (pinfunction "1_1") (pintype "passive"))
      (node (ref "SWD4") (pin "2") (pinfunction "2_2") (pintype "passive"))
    )
    (net (code "31") (name "Net-(C403-Pad1)") (class "Default")
      (node (ref "C403") (pin "1") (pinfunction "1_1") (pintype "passive"))
      (node (ref "SWD4") (pin "1") (pinfunction "1_1") (pintype "passive"))
    )
    (net (code "32") (name "Net-(E1-A)") (class "Default")
      (node (ref "C25") (pin "1") (pinfunction "1_1") (pintype "passive"))
      (node (ref "E1") (pin "1") (pinfunction "A_1") (pintype "passive"))
      (node (ref "K1") (pin "3") (pinfunction "V+_3") (pintype "passive"))
      (node (ref "PR1") (pin "1") (pinfunction "Vo+_1") (pintype "passive"))
      (node (ref "V1") (pin "3") (pinfunction "V+_3") (pintype "passive"))
    )
    (net (code "33") (name "Net-(E2-K)") (class "Default")
      (node (ref "C26") (pin "1") (pinfunction "1_1") (pintype "passive"))
      (node (ref "E2") (pin "2") (pinfunction "K_2") (pintype "passive"))
      (node (ref "K1") (pin "4") (pinfunction "V-_4") (pintype "passive"))
      (node (ref "PR1") (pin "2") (pinfunction "Vo-_2") (pintype "passive"))
      (node (ref "V1") (pin "4") (pinfunction "V-_4") (pintype "passive"))
    )
    (net (code "34") (name "Net-(E3-A)") (class "Default")
      (node (ref "C27") (pin "1") (pinfunction "1_1") (pintype "passive"))
      (node (ref "E3") (pin "1") (pinfunction "A_1") (pintype "passive"))
      (node (ref "K2") (pin "3") (pinfunction "V+_3") (pintype "passive"))
      (node (ref "PR2") (pin "1") (pinfunction "Vo+_1") (pintype "passive"))
      (node (ref "V2") (pin "3") (pinfunction "V+_3") (pintype "passive"))
    )
    (net (code "35") (name "Net-(E4-K)") (class "Default")
      (node (ref "C28") (pin "1") (pinfunction "1_1") (pintype "passive"))
      (node (ref "E4") (pin "2") (pinfunction "K_2") (pintype "passive"))
      (node (ref "K2") (pin "4") (pinfunction "V-_4") (pintype "passive"))
      (node (ref "PR2") (pin "2") (pinfunction "Vo-_2") (pintype "passive"))
      (node (ref "V2") (pin "4") (pinfunction "V-_4") (pintype "passive"))
    )
    (net (code "36") (name "Net-(K1-In)") (class "Default")
      (node (ref "C4") (pin "1") (pinfunction "1_1") (pintype "passive"))
      (node (ref "K1") (pin "1") (pinfunction "In_1") (pintype "passive"))
      (node (ref "R5") (pin "1") (pinfunction "1_1") (pintype "passive"))
    )
    (net (code "37") (name "Net-(K1-Out)") (class "Default")
      (node (ref "C10") (pin "2") (pinfunction "2_2") (pintype "passive"))
      (node (ref "K1") (pin "2") (pinfunction "Out_2") (pintype "passive"))
      (node (ref "R11") (pin "1") (pinfunction "1_1") (pintype "passive"))
      (node (ref "R7") (pin "1") (pinfunction "1_1") (pintype "passive"))
      (node (ref "R9") (pin "1") (pinfunction "1_1") (pintype "passive"))
    )
    (net (code "38") (name "Net-(K2-In)") (class "Default")
      (node (ref "C16") (pin "1") (pinfunction "1_1") (pintype "passive"))
      (node (ref "K2") (pin "1") (pinfunction "In_1") (pintype "passive"))
      (node (ref "R20") (pin "2") (pinfunction "2_2") (pintype "passive"))
    )
    (net (code "39") (name "Net-(K2-Out)") (class "Default")
      (node (ref "C24") (pin "1") (pinfunction "1_1") (pintype "passive"))
      (node (ref "K2") (pin "2") (pinfunction "Out_2") (pintype "passive"))
      (node (ref "R22") (pin "2") (pinfunction "2_2") (pintype "passive"))
      (node (ref "R24") (pin "2") (pinfunction "2_2") (pintype "passive"))
      (node (ref "R27") (pin "1") (pinfunction "1_1") (pintype "passive"))
    )
    (net (code "40") (name "Net-(O1-Out)") (class "Default")
      (node (ref "C5") (pin "1") (pinfunction "1_1") (pintype "passive"))
      (node (ref "C5") (pin "2") (pinfunction "2_2") (pintype "passive"))
      (node (ref "C6") (pin "2") (pinfunction "2_2") (pintype "passive"))
      (node (ref "O1") (pin "1") (pinfunction "Out_1") (pintype "passive"))
      (node (ref "R7") (pin "2") (pinfunction "2_2") (pintype "passive"))
      (node (ref "R8") (pin "2") (pinfunction "2_2") (pintype "passive"))
    )
    (net (code "41") (name "Net-(O2-Out)") (class "Default")
      (node (ref "C17") (pin "1") (pinfunction "1_1") (pintype "passive"))
      (node (ref "C17") (pin "2") (pinfunction "2_2") (pintype "passive"))
      (node (ref "C18") (pin "1") (pinfunction "1_1") (pintype "passive"))
      (node (ref "O2") (pin "1") (pinfunction "Out_1") (pintype "passive"))
      (node (ref "R22") (pin "1") (pinfunction "1_1") (pintype "passive"))
      (node (ref "R23") (pin "1") (pinfunction "1_1") (pintype "passive"))
    )
    (net (code "42") (name "Net-(R1-Pad1)") (class "Default")
      (node (ref "R1") (pin "1") (pinfunction "1_1") (pintype "passive"))
      (node (ref "SWD5") (pin "4") (pinfunction "4_4") (pintype "passive"))
    )
    (net (code "43") (name "Net-(R10-Pad1)") (class "Default")
      (node (ref "R10") (pin "1") (pinfunction "1_1") (pintype "passive"))
      (node (ref "R16") (pin "2") (pinfunction "2_2") (pintype "passive"))
      (node (ref "R9") (pin "2") (pinfunction "2_2") (pintype "passive"))
    )
    (net (code "44") (name "Net-(R11-Pad2)") (class "Default")
      (node (ref "R11") (pin "2") (pinfunction "2_2") (pintype "passive"))
      (node (ref "VR1") (pin "1") (pinfunction "1_1") (pintype "passive"))
      (node (ref "VR1") (pin "3") (pinfunction "3_3") (pintype "passive"))
    )
    (net (code "45") (name "Net-(R12-Pad1)") (class "Default")
      (node (ref "R12") (pin "1") (pinfunction "1_1") (pintype "passive"))
      (node (ref "R13") (pin "1") (pinfunction "1_1") (pintype "passive"))
      (node (ref "SW1") (pin "1") (pinfunction "1_1") (pintype "passive"))
    )
    (net (code "46") (name "Net-(R12-Pad2)") (class "Default")
      (node (ref "R12") (pin "2") (pinfunction "2_2") (pintype "passive"))
      (node (ref "SW1") (pin "2") (pinfunction "2_2") (pintype "passive"))
      (node (ref "VR2") (pin "2") (pinfunction "2_2") (pintype "passive"))
    )
    (net (code "47") (name "Net-(R18-Pad1)") (class "Default")
      (node (ref "R18") (pin "1") (pinfunction "1_1") (pintype "passive"))
      (node (ref "SWD6") (pin "4") (pinfunction "4_4") (pintype "passive"))
    )
    (net (code "48") (name "Net-(R24-Pad1)") (class "Default")
      (node (ref "R24") (pin "1") (pinfunction "1_1") (pintype "passive"))
      (node (ref "R25") (pin "2") (pinfunction "2_2") (pintype "passive"))
      (node (ref "R26") (pin "2") (pinfunction "2_2") (pintype "passive"))
    )
    (net (code "49") (name "Net-(R27-Pad2)") (class "Default")
      (node (ref "R27") (pin "2") (pinfunction "2_2") (pintype "passive"))
      (node (ref "VR3") (pin "1") (pinfunction "1_1") (pintype "passive"))
      (node (ref "VR3") (pin "3") (pinfunction "3_3") (pintype "passive"))
    )
    (net (code "50") (name "Net-(R28-Pad1)") (class "Default")
      (node (ref "R28") (pin "1") (pinfunction "1_1") (pintype "passive"))
      (node (ref "R29") (pin "1") (pinfunction "1_1") (pintype "passive"))
      (node (ref "SW2") (pin "1") (pinfunction "1_1") (pintype "passive"))
    )
    (net (code "51") (name "Net-(R28-Pad2)") (class "Default")
      (node (ref "R28") (pin "2") (pinfunction "2_2") (pintype "passive"))
      (node (ref "SW2") (pin "2") (pinfunction "2_2") (pintype "passive"))
      (node (ref "VR4") (pin "2") (pinfunction "2_2") (pintype "passive"))
    )
    (net (code "52") (name "Net-(R101-Pad1)") (class "Default")
      (node (ref "R101") (pin "1") (pinfunction "1_1") (pintype "passive"))
      (node (ref "SWD5") (pin "3") (pinfunction "3_3") (pintype "passive"))
    )
    (net (code "53") (name "Net-(R102-Pad1)") (class "Default")
      (node (ref "R102") (pin "1") (pinfunction "1_1") (pintype "passive"))
      (node (ref "SWD5") (pin "2") (pinfunction "2_2") (pintype "passive"))
    )
    (net (code "54") (name "Net-(R103-Pad1)") (class "Default")
      (node (ref "R103") (pin "1") (pinfunction "1_1") (pintype "passive"))
      (node (ref "SWD5") (pin "1") (pinfunction "1_1") (pintype "passive"))
    )
    (net (code "55") (name "Net-(R181-Pad1)") (class "Default")
      (node (ref "R181") (pin "1") (pinfunction "1_1") (pintype "passive"))
      (node (ref "SWD6") (pin "3") (pinfunction "3_3") (pintype "passive"))
    )
    (net (code "56") (name "Net-(R182-Pad1)") (class "Default")
      (node (ref "R182") (pin "1") (pinfunction "1_1") (pintype "passive"))
      (node (ref "SWD6") (pin "2") (pinfunction "2_2") (pintype "passive"))
    )
    (net (code "57") (name "Net-(R183-Pad1)") (class "Default")
      (node (ref "R183") (pin "1") (pinfunction "1_1") (pintype "passive"))
      (node (ref "SWD6") (pin "1") (pinfunction "1_1") (pintype "passive"))
    )
    (net (code "58") (name "Net-(S1-In)") (class "Default")
      (node (ref "C1") (pin "1") (pinfunction "1_1") (pintype "passive"))
      (node (ref "S1") (pin "1") (pinfunction "In_1") (pintype "passive"))
    )
    (net (code "59") (name "Net-(S2-In)") (class "Default")
      (node (ref "C13") (pin "1") (pinfunction "1_1") (pintype "passive"))
      (node (ref "S2") (pin "1") (pinfunction "In_1") (pintype "passive"))
    )
    (net (code "60") (name "Net-(SW1-Pad3)") (class "Default")
      (node (ref "SW1") (pin "3") (pinfunction "3_3") (pintype "passive"))
      (node (ref "VR1") (pin "2") (pinfunction "2_2") (pintype "passive"))
    )
    (net (code "61") (name "Net-(SW2-Pad3)") (class "Default")
      (node (ref "SW2") (pin "3") (pinfunction "3_3") (pintype "passive"))
      (node (ref "VR3") (pin "2") (pinfunction "2_2") (pintype "passive"))
    )
    (net (code "62") (name "Net-(V1-In+)") (class "Default")
      (node (ref "R3") (pin "1") (pinfunction "1_1") (pintype "passive"))
      (node (ref "V1") (pin "1") (pinfunction "In+_1") (pintype "passive"))
    )
    (net (code "63") (name "Net-(V1-In-)") (class "Default")
      (node (ref "R4") (pin "2") (pinfunction "2_2") (pintype "passive"))
      (node (ref "V1") (pin "2") (pinfunction "In-_2") (pintype "passive"))
    )
    (net (code "64") (name "Net-(V1-Out)") (class "Default")
      (node (ref "C100") (pin "2") (pinfunction "2_2") (pintype "passive"))
      (node (ref "C101") (pin "2") (pinfunction "2_2") (pintype "passive"))
      (node (ref "C102") (pin "2") (pinfunction "2_2") (pintype "passive"))
      (node (ref "C103") (pin "2") (pinfunction "2_2") (pintype "passive"))
      (node (ref "R5") (pin "2") (pinfunction "2_2") (pintype "passive"))
      (node (ref "V1") (pin "6") (pinfunction "Out_6") (pintype "passive"))
    )
    (net (code "65") (name "Net-(V2-In+)") (class "Default")
      (node (ref "R19") (pin "2") (pinfunction "2_2") (pintype "passive"))
      (node (ref "V2") (pin "1") (pinfunction "In+_1") (pintype "passive"))
    )
    (net (code "66") (name "Net-(V2-In-)") (class "Default")
      (node (ref "R32") (pin "2") (pinfunction "2_2") (pintype "passive"))
      (node (ref "V2") (pin "2") (pinfunction "In-_2") (pintype "passive"))
    )
    (net (code "67") (name "Net-(V2-Out)") (class "Default")
      (node (ref "C15") (pin "2") (pinfunction "2_2") (pintype "passive"))
      (node (ref "C401") (pin "2") (pinfunction "2_2") (pintype "passive"))
      (node (ref "C402") (pin "2") (pinfunction "2_2") (pintype "passive"))
      (node (ref "C403") (pin "2") (pinfunction "2_2") (pintype "passive"))
      (node (ref "R20") (pin "1") (pinfunction "1_1") (pintype "passive"))
      (node (ref "V2") (pin "6") (pinfunction "Out_6") (pintype "passive"))
    )
  )
)
